# 2_matrix.net
KiCad netlist of a schematic drawn in Altium Designer
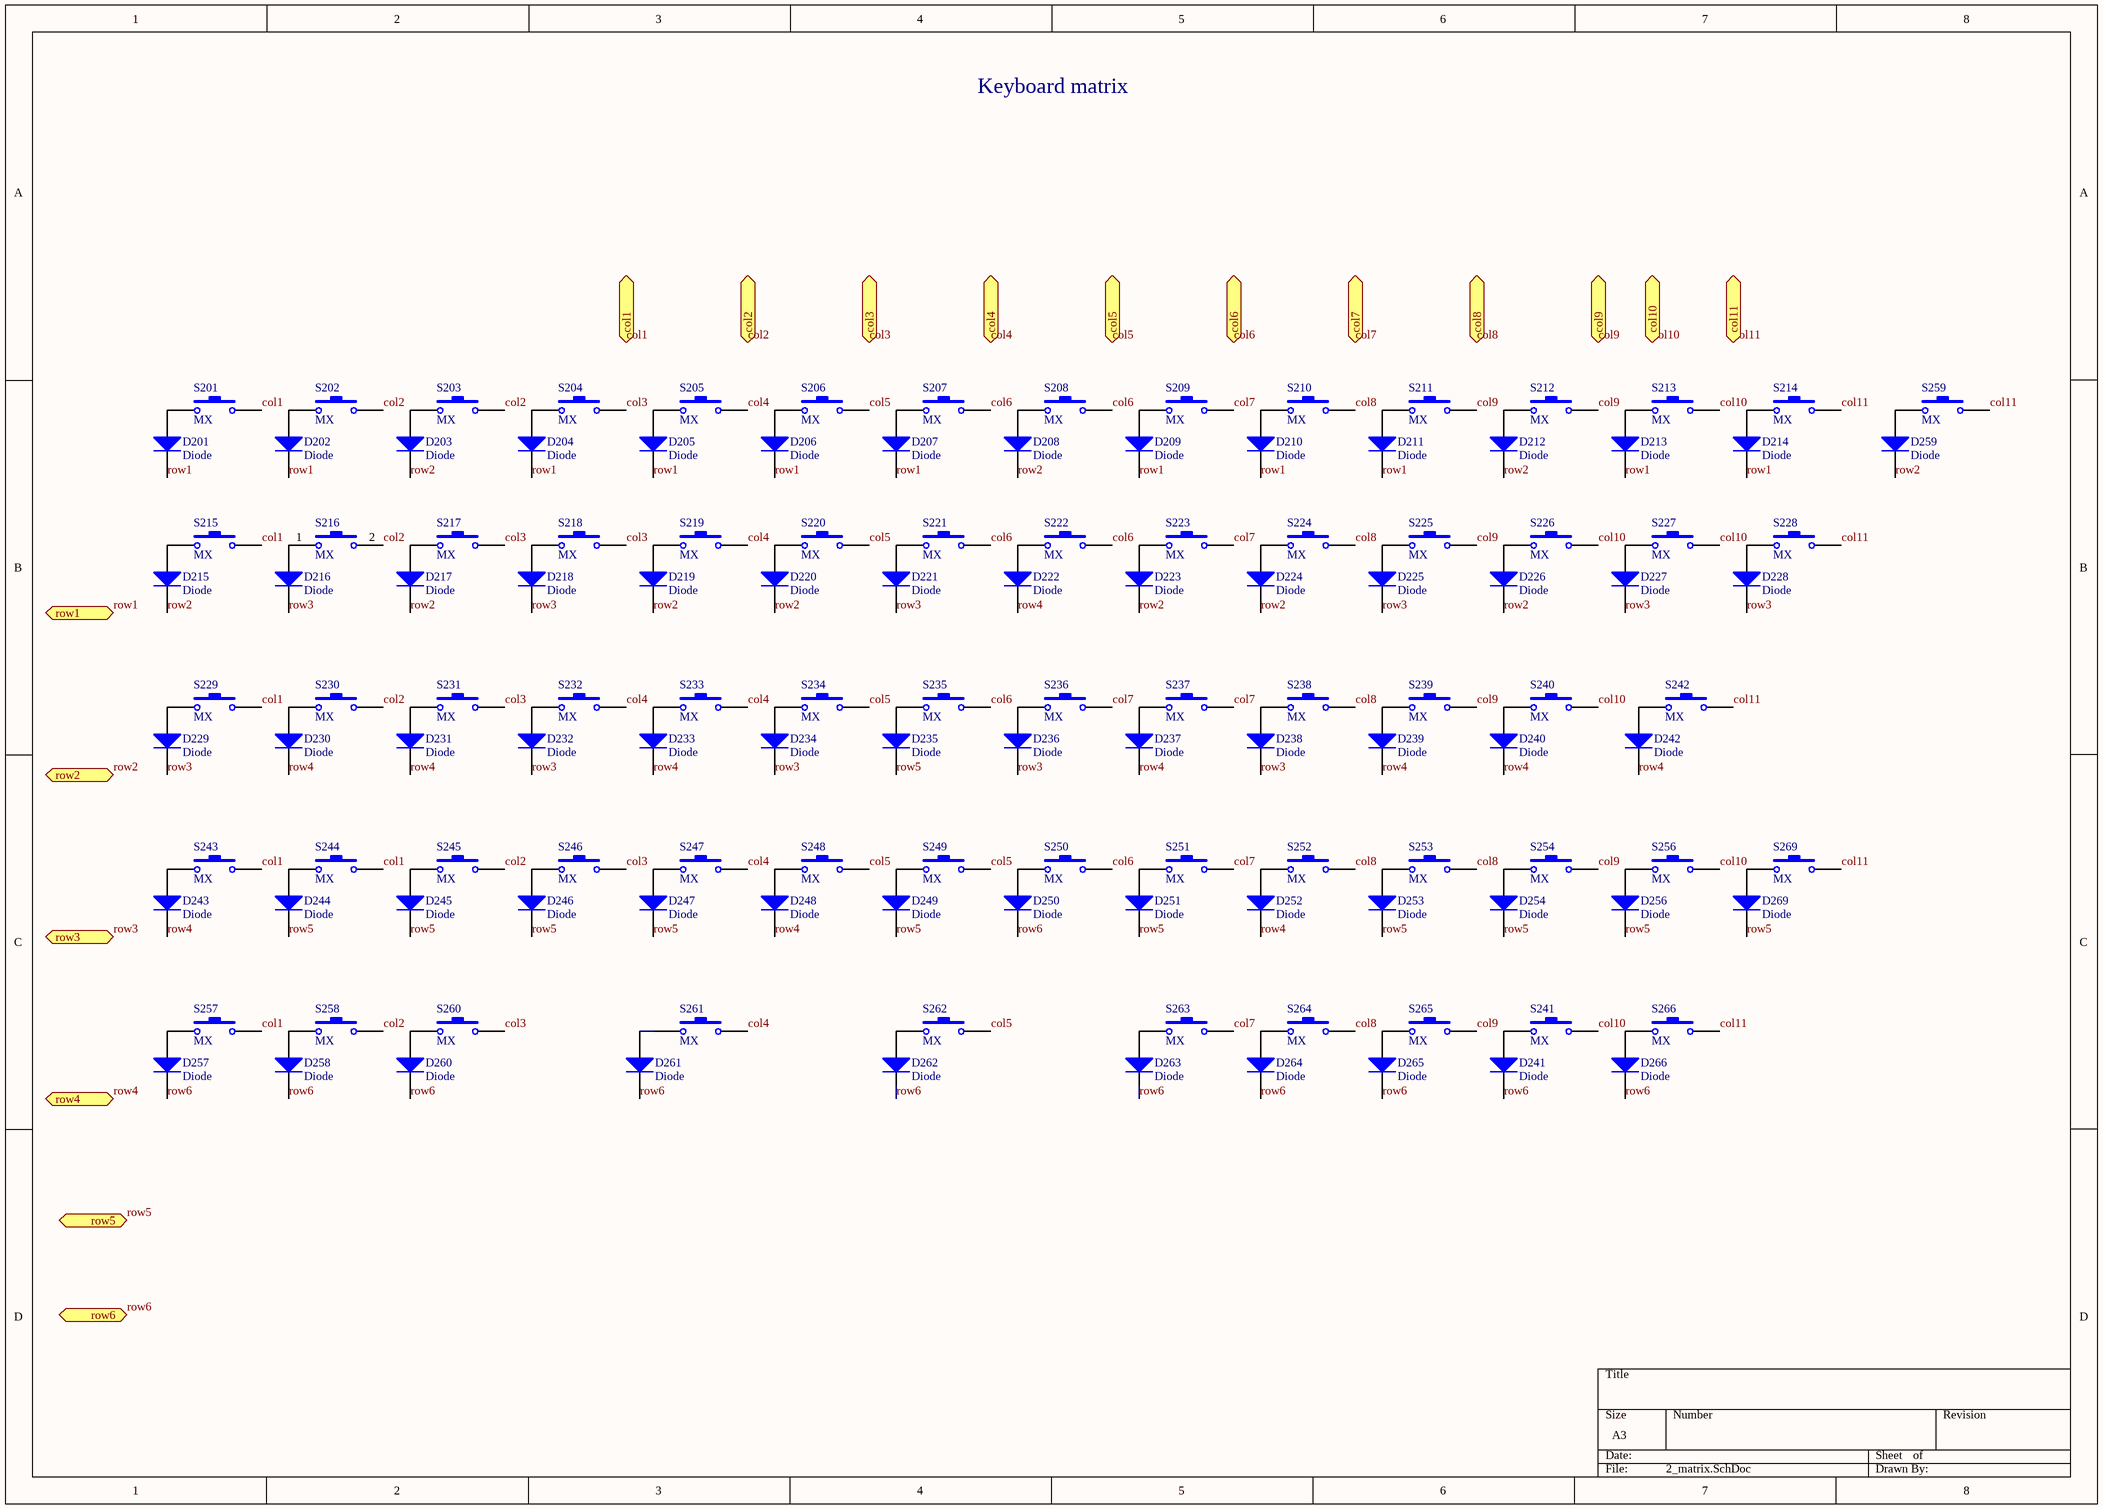
[diagram p0: 2_matrix.SchDoc]

(export (version "E")
  (design (tool "Eeschema 10.0.6"))
  (components
    (comp (ref "D201")
      (value "Diode")
      (footprint "D0603[1608]")
      (description "Default Diode")
      (fields (field (name "MFG") "Bourns Inc.") (field (name "MRF.PART") "CD4148WTP"))
      (libsource (lib "Miscellaneous Devices") (part "Diode"))
    )
    (comp (ref "D202")
      (value "Diode")
      (footprint "D0603[1608]")
      (description "Default Diode")
      (fields (field (name "MFG") "Bourns Inc.") (field (name "MRF.PART") "CD4148WTP"))
      (libsource (lib "Miscellaneous Devices") (part "Diode"))
    )
    (comp (ref "D203")
      (value "Diode")
      (footprint "D0603[1608]")
      (description "Default Diode")
      (fields (field (name "MFG") "Bourns Inc.") (field (name "MRF.PART") "CD4148WTP"))
      (libsource (lib "Miscellaneous Devices") (part "Diode"))
    )
    (comp (ref "D204")
      (value "Diode")
      (footprint "D0603[1608]")
      (description "Default Diode")
      (fields (field (name "MFG") "Bourns Inc.") (field (name "MRF.PART") "CD4148WTP"))
      (libsource (lib "Miscellaneous Devices") (part "Diode"))
    )
    (comp (ref "D205")
      (value "Diode")
      (footprint "D0603[1608]")
      (description "Default Diode")
      (fields (field (name "MFG") "Bourns Inc.") (field (name "MRF.PART") "CD4148WTP"))
      (libsource (lib "Miscellaneous Devices") (part "Diode"))
    )
    (comp (ref "D206")
      (value "Diode")
      (footprint "D0603[1608]")
      (description "Default Diode")
      (fields (field (name "MFG") "Bourns Inc.") (field (name "MRF.PART") "CD4148WTP"))
      (libsource (lib "Miscellaneous Devices") (part "Diode"))
    )
    (comp (ref "D207")
      (value "Diode")
      (footprint "D0603[1608]")
      (description "Default Diode")
      (fields (field (name "MFG") "Bourns Inc.") (field (name "MRF.PART") "CD4148WTP"))
      (libsource (lib "Miscellaneous Devices") (part "Diode"))
    )
    (comp (ref "D208")
      (value "Diode")
      (footprint "D0603[1608]")
      (description "Default Diode")
      (fields (field (name "MFG") "Bourns Inc.") (field (name "MRF.PART") "CD4148WTP"))
      (libsource (lib "Miscellaneous Devices") (part "Diode"))
    )
    (comp (ref "D209")
      (value "Diode")
      (footprint "D0603[1608]")
      (description "Default Diode")
      (fields (field (name "MFG") "Bourns Inc.") (field (name "MRF.PART") "CD4148WTP"))
      (libsource (lib "Miscellaneous Devices") (part "Diode"))
    )
    (comp (ref "D210")
      (value "Diode")
      (footprint "D0603[1608]")
      (description "Default Diode")
      (fields (field (name "MFG") "Bourns Inc.") (field (name "MRF.PART") "CD4148WTP"))
      (libsource (lib "Miscellaneous Devices") (part "Diode"))
    )
    (comp (ref "D211")
      (value "Diode")
      (footprint "D0603[1608]")
      (description "Default Diode")
      (fields (field (name "MFG") "Bourns Inc.") (field (name "MRF.PART") "CD4148WTP"))
      (libsource (lib "Miscellaneous Devices") (part "Diode"))
    )
    (comp (ref "D212")
      (value "Diode")
      (footprint "D0603[1608]")
      (description "Default Diode")
      (fields (field (name "MFG") "Bourns Inc.") (field (name "MRF.PART") "CD4148WTP"))
      (libsource (lib "Miscellaneous Devices") (part "Diode"))
    )
    (comp (ref "D213")
      (value "Diode")
      (footprint "D0603[1608]")
      (description "Default Diode")
      (fields (field (name "MFG") "Bourns Inc.") (field (name "MRF.PART") "CD4148WTP"))
      (libsource (lib "Miscellaneous Devices") (part "Diode"))
    )
    (comp (ref "D214")
      (value "Diode")
      (footprint "D0603[1608]")
      (description "Default Diode")
      (fields (field (name "MFG") "Bourns Inc.") (field (name "MRF.PART") "CD4148WTP"))
      (libsource (lib "Miscellaneous Devices") (part "Diode"))
    )
    (comp (ref "D215")
      (value "Diode")
      (footprint "D0603[1608]")
      (description "Default Diode")
      (fields (field (name "MFG") "Bourns Inc.") (field (name "MRF.PART") "CD4148WTP"))
      (libsource (lib "Miscellaneous Devices") (part "Diode"))
    )
    (comp (ref "D216")
      (value "Diode")
      (footprint "D0603[1608]")
      (description "Default Diode")
      (fields (field (name "MFG") "Bourns Inc.") (field (name "MRF.PART") "CD4148WTP"))
      (libsource (lib "Miscellaneous Devices") (part "Diode"))
    )
    (comp (ref "D217")
      (value "Diode")
      (footprint "D0603[1608]")
      (description "Default Diode")
      (fields (field (name "MFG") "Bourns Inc.") (field (name "MRF.PART") "CD4148WTP"))
      (libsource (lib "Miscellaneous Devices") (part "Diode"))
    )
    (comp (ref "D218")
      (value "Diode")
      (footprint "D0603[1608]")
      (description "Default Diode")
      (fields (field (name "MFG") "Bourns Inc.") (field (name "MRF.PART") "CD4148WTP"))
      (libsource (lib "Miscellaneous Devices") (part "Diode"))
    )
    (comp (ref "D219")
      (value "Diode")
      (footprint "D0603[1608]")
      (description "Default Diode")
      (fields (field (name "MFG") "Bourns Inc.") (field (name "MRF.PART") "CD4148WTP"))
      (libsource (lib "Miscellaneous Devices") (part "Diode"))
    )
    (comp (ref "D220")
      (value "Diode")
      (footprint "D0603[1608]")
      (description "Default Diode")
      (fields (field (name "MFG") "Bourns Inc.") (field (name "MRF.PART") "CD4148WTP"))
      (libsource (lib "Miscellaneous Devices") (part "Diode"))
    )
    (comp (ref "D221")
      (value "Diode")
      (footprint "D0603[1608]")
      (description "Default Diode")
      (fields (field (name "MFG") "Bourns Inc.") (field (name "MRF.PART") "CD4148WTP"))
      (libsource (lib "Miscellaneous Devices") (part "Diode"))
    )
    (comp (ref "D222")
      (value "Diode")
      (footprint "D0603[1608]")
      (description "Default Diode")
      (fields (field (name "MFG") "Bourns Inc.") (field (name "MRF.PART") "CD4148WTP"))
      (libsource (lib "Miscellaneous Devices") (part "Diode"))
    )
    (comp (ref "D223")
      (value "Diode")
      (footprint "D0603[1608]")
      (description "Default Diode")
      (fields (field (name "MFG") "Bourns Inc.") (field (name "MRF.PART") "CD4148WTP"))
      (libsource (lib "Miscellaneous Devices") (part "Diode"))
    )
    (comp (ref "D224")
      (value "Diode")
      (footprint "D0603[1608]")
      (description "Default Diode")
      (fields (field (name "MFG") "Bourns Inc.") (field (name "MRF.PART") "CD4148WTP"))
      (libsource (lib "Miscellaneous Devices") (part "Diode"))
    )
    (comp (ref "D225")
      (value "Diode")
      (footprint "D0603[1608]")
      (description "Default Diode")
      (fields (field (name "MFG") "Bourns Inc.") (field (name "MRF.PART") "CD4148WTP"))
      (libsource (lib "Miscellaneous Devices") (part "Diode"))
    )
    (comp (ref "D226")
      (value "Diode")
      (footprint "D0603[1608]")
      (description "Default Diode")
      (fields (field (name "MFG") "Bourns Inc.") (field (name "MRF.PART") "CD4148WTP"))
      (libsource (lib "Miscellaneous Devices") (part "Diode"))
    )
    (comp (ref "D227")
      (value "Diode")
      (footprint "D0603[1608]")
      (description "Default Diode")
      (fields (field (name "MFG") "Bourns Inc.") (field (name "MRF.PART") "CD4148WTP"))
      (libsource (lib "Miscellaneous Devices") (part "Diode"))
    )
    (comp (ref "D228")
      (value "Diode")
      (footprint "D0603[1608]")
      (description "Default Diode")
      (fields (field (name "MFG") "Bourns Inc.") (field (name "MRF.PART") "CD4148WTP"))
      (libsource (lib "Miscellaneous Devices") (part "Diode"))
    )
    (comp (ref "D229")
      (value "Diode")
      (footprint "D0603[1608]")
      (description "Default Diode")
      (fields (field (name "MFG") "Bourns Inc.") (field (name "MRF.PART") "CD4148WTP"))
      (libsource (lib "Miscellaneous Devices") (part "Diode"))
    )
    (comp (ref "D230")
      (value "Diode")
      (footprint "D0603[1608]")
      (description "Default Diode")
      (fields (field (name "MFG") "Bourns Inc.") (field (name "MRF.PART") "CD4148WTP"))
      (libsource (lib "Miscellaneous Devices") (part "Diode"))
    )
    (comp (ref "D231")
      (value "Diode")
      (footprint "D0603[1608]")
      (description "Default Diode")
      (fields (field (name "MFG") "Bourns Inc.") (field (name "MRF.PART") "CD4148WTP"))
      (libsource (lib "Miscellaneous Devices") (part "Diode"))
    )
    (comp (ref "D232")
      (value "Diode")
      (footprint "D0603[1608]")
      (description "Default Diode")
      (fields (field (name "MFG") "Bourns Inc.") (field (name "MRF.PART") "CD4148WTP"))
      (libsource (lib "Miscellaneous Devices") (part "Diode"))
    )
    (comp (ref "D233")
      (value "Diode")
      (footprint "D0603[1608]")
      (description "Default Diode")
      (fields (field (name "MFG") "Bourns Inc.") (field (name "MRF.PART") "CD4148WTP"))
      (libsource (lib "Miscellaneous Devices") (part "Diode"))
    )
    (comp (ref "D234")
      (value "Diode")
      (footprint "D0603[1608]")
      (description "Default Diode")
      (fields (field (name "MFG") "Bourns Inc.") (field (name "MRF.PART") "CD4148WTP"))
      (libsource (lib "Miscellaneous Devices") (part "Diode"))
    )
    (comp (ref "D235")
      (value "Diode")
      (footprint "D0603[1608]")
      (description "Default Diode")
      (fields (field (name "MFG") "Bourns Inc.") (field (name "MRF.PART") "CD4148WTP"))
      (libsource (lib "Miscellaneous Devices") (part "Diode"))
    )
    (comp (ref "D236")
      (value "Diode")
      (footprint "D0603[1608]")
      (description "Default Diode")
      (fields (field (name "MFG") "Bourns Inc.") (field (name "MRF.PART") "CD4148WTP"))
      (libsource (lib "Miscellaneous Devices") (part "Diode"))
    )
    (comp (ref "D237")
      (value "Diode")
      (footprint "D0603[1608]")
      (description "Default Diode")
      (fields (field (name "MFG") "Bourns Inc.") (field (name "MRF.PART") "CD4148WTP"))
      (libsource (lib "Miscellaneous Devices") (part "Diode"))
    )
    (comp (ref "D238")
      (value "Diode")
      (footprint "D0603[1608]")
      (description "Default Diode")
      (fields (field (name "MFG") "Bourns Inc.") (field (name "MRF.PART") "CD4148WTP"))
      (libsource (lib "Miscellaneous Devices") (part "Diode"))
    )
    (comp (ref "D239")
      (value "Diode")
      (footprint "D0603[1608]")
      (description "Default Diode")
      (fields (field (name "MFG") "Bourns Inc.") (field (name "MRF.PART") "CD4148WTP"))
      (libsource (lib "Miscellaneous Devices") (part "Diode"))
    )
    (comp (ref "D240")
      (value "Diode")
      (footprint "D0603[1608]")
      (description "Default Diode")
      (fields (field (name "MFG") "Bourns Inc.") (field (name "MRF.PART") "CD4148WTP"))
      (libsource (lib "Miscellaneous Devices") (part "Diode"))
    )
    (comp (ref "D241")
      (value "Diode")
      (footprint "D0603[1608]")
      (description "Default Diode")
      (fields (field (name "MFG") "Bourns Inc.") (field (name "MRF.PART") "CD4148WTP"))
      (libsource (lib "Miscellaneous Devices") (part "Diode"))
    )
    (comp (ref "D242")
      (value "Diode")
      (footprint "D0603[1608]")
      (description "Default Diode")
      (fields (field (name "MFG") "Bourns Inc.") (field (name "MRF.PART") "CD4148WTP"))
      (libsource (lib "Miscellaneous Devices") (part "Diode"))
    )
    (comp (ref "D243")
      (value "Diode")
      (footprint "D0603[1608]")
      (description "Default Diode")
      (fields (field (name "MFG") "Bourns Inc.") (field (name "MRF.PART") "CD4148WTP"))
      (libsource (lib "Miscellaneous Devices") (part "Diode"))
    )
    (comp (ref "D244")
      (value "Diode")
      (footprint "D0603[1608]")
      (description "Default Diode")
      (fields (field (name "MFG") "Bourns Inc.") (field (name "MRF.PART") "CD4148WTP"))
      (libsource (lib "Miscellaneous Devices") (part "Diode"))
    )
    (comp (ref "D245")
      (value "Diode")
      (footprint "D0603[1608]")
      (description "Default Diode")
      (fields (field (name "MFG") "Bourns Inc.") (field (name "MRF.PART") "CD4148WTP"))
      (libsource (lib "Miscellaneous Devices") (part "Diode"))
    )
    (comp (ref "D246")
      (value "Diode")
      (footprint "D0603[1608]")
      (description "Default Diode")
      (fields (field (name "MFG") "Bourns Inc.") (field (name "MRF.PART") "CD4148WTP"))
      (libsource (lib "Miscellaneous Devices") (part "Diode"))
    )
    (comp (ref "D247")
      (value "Diode")
      (footprint "D0603[1608]")
      (description "Default Diode")
      (fields (field (name "MFG") "Bourns Inc.") (field (name "MRF.PART") "CD4148WTP"))
      (libsource (lib "Miscellaneous Devices") (part "Diode"))
    )
    (comp (ref "D248")
      (value "Diode")
      (footprint "D0603[1608]")
      (description "Default Diode")
      (fields (field (name "MFG") "Bourns Inc.") (field (name "MRF.PART") "CD4148WTP"))
      (libsource (lib "Miscellaneous Devices") (part "Diode"))
    )
    (comp (ref "D249")
      (value "Diode")
      (footprint "D0603[1608]")
      (description "Default Diode")
      (fields (field (name "MFG") "Bourns Inc.") (field (name "MRF.PART") "CD4148WTP"))
      (libsource (lib "Miscellaneous Devices") (part "Diode"))
    )
    (comp (ref "D250")
      (value "Diode")
      (footprint "D0603[1608]")
      (description "Default Diode")
      (fields (field (name "MFG") "Bourns Inc.") (field (name "MRF.PART") "CD4148WTP"))
      (libsource (lib "Miscellaneous Devices") (part "Diode"))
    )
    (comp (ref "D251")
      (value "Diode")
      (footprint "D0603[1608]")
      (description "Default Diode")
      (fields (field (name "MFG") "Bourns Inc.") (field (name "MRF.PART") "CD4148WTP"))
      (libsource (lib "Miscellaneous Devices") (part "Diode"))
    )
    (comp (ref "D252")
      (value "Diode")
      (footprint "D0603[1608]")
      (description "Default Diode")
      (fields (field (name "MFG") "Bourns Inc.") (field (name "MRF.PART") "CD4148WTP"))
      (libsource (lib "Miscellaneous Devices") (part "Diode"))
    )
    (comp (ref "D253")
      (value "Diode")
      (footprint "D0603[1608]")
      (description "Default Diode")
      (fields (field (name "MFG") "Bourns Inc.") (field (name "MRF.PART") "CD4148WTP"))
      (libsource (lib "Miscellaneous Devices") (part "Diode"))
    )
    (comp (ref "D254")
      (value "Diode")
      (footprint "D0603[1608]")
      (description "Default Diode")
      (fields (field (name "MFG") "Bourns Inc.") (field (name "MRF.PART") "CD4148WTP"))
      (libsource (lib "Miscellaneous Devices") (part "Diode"))
    )
    (comp (ref "D256")
      (value "Diode")
      (footprint "D0603[1608]")
      (description "Default Diode")
      (fields (field (name "MFG") "Bourns Inc.") (field (name "MRF.PART") "CD4148WTP"))
      (libsource (lib "Miscellaneous Devices") (part "Diode"))
    )
    (comp (ref "D257")
      (value "Diode")
      (footprint "D0603[1608]")
      (description "Default Diode")
      (fields (field (name "MFG") "Bourns Inc.") (field (name "MRF.PART") "CD4148WTP"))
      (libsource (lib "Miscellaneous Devices") (part "Diode"))
    )
    (comp (ref "D258")
      (value "Diode")
      (footprint "D0603[1608]")
      (description "Default Diode")
      (fields (field (name "MFG") "Bourns Inc.") (field (name "MRF.PART") "CD4148WTP"))
      (libsource (lib "Miscellaneous Devices") (part "Diode"))
    )
    (comp (ref "D259")
      (value "Diode")
      (footprint "D0603[1608]")
      (description "Default Diode")
      (fields (field (name "MFG") "Bourns Inc.") (field (name "MRF.PART") "CD4148WTP"))
      (libsource (lib "Miscellaneous Devices") (part "Diode"))
    )
    (comp (ref "D260")
      (value "Diode")
      (footprint "D0603[1608]")
      (description "Default Diode")
      (fields (field (name "MFG") "Bourns Inc.") (field (name "MRF.PART") "CD4148WTP"))
      (libsource (lib "Miscellaneous Devices") (part "Diode"))
    )
    (comp (ref "D261")
      (value "Diode")
      (footprint "D0603[1608]")
      (description "Default Diode")
      (fields (field (name "MFG") "Bourns Inc.") (field (name "MRF.PART") "CD4148WTP"))
      (libsource (lib "Miscellaneous Devices") (part "Diode"))
    )
    (comp (ref "D262")
      (value "Diode")
      (footprint "D0603[1608]")
      (description "Default Diode")
      (fields (field (name "MFG") "Bourns Inc.") (field (name "MRF.PART") "CD4148WTP"))
      (libsource (lib "Miscellaneous Devices") (part "Diode"))
    )
    (comp (ref "D263")
      (value "Diode")
      (footprint "D0603[1608]")
      (description "Default Diode")
      (fields (field (name "MFG") "Bourns Inc.") (field (name "MRF.PART") "CD4148WTP"))
      (libsource (lib "Miscellaneous Devices") (part "Diode"))
    )
    (comp (ref "D264")
      (value "Diode")
      (footprint "D0603[1608]")
      (description "Default Diode")
      (fields (field (name "MFG") "Bourns Inc.") (field (name "MRF.PART") "CD4148WTP"))
      (libsource (lib "Miscellaneous Devices") (part "Diode"))
    )
    (comp (ref "D265")
      (value "Diode")
      (footprint "D0603[1608]")
      (description "Default Diode")
      (fields (field (name "MFG") "Bourns Inc.") (field (name "MRF.PART") "CD4148WTP"))
      (libsource (lib "Miscellaneous Devices") (part "Diode"))
    )
    (comp (ref "D266")
      (value "Diode")
      (footprint "D0603[1608]")
      (description "Default Diode")
      (fields (field (name "MFG") "Bourns Inc.") (field (name "MRF.PART") "CD4148WTP"))
      (libsource (lib "Miscellaneous Devices") (part "Diode"))
    )
    (comp (ref "D269")
      (value "Diode")
      (footprint "D0603[1608]")
      (description "Default Diode")
      (fields (field (name "MFG") "Bourns Inc.") (field (name "MRF.PART") "CD4148WTP"))
      (libsource (lib "Miscellaneous Devices") (part "Diode"))
    )
    (comp (ref "S201")
      (value "MX")
      (footprint "MXHS-switch")
      (description "Switch")
      (libsource (lib "Miscellaneous Devices") (part "SW-PB"))
    )
    (comp (ref "S202")
      (value "MX")
      (footprint "MXHS-switch")
      (description "Switch")
      (libsource (lib "Miscellaneous Devices") (part "SW-PB"))
    )
    (comp (ref "S203")
      (value "MX")
      (footprint "MXHS-switch")
      (description "Switch")
      (libsource (lib "Miscellaneous Devices") (part "SW-PB"))
    )
    (comp (ref "S204")
      (value "MX")
      (footprint "MXHS-switch")
      (description "Switch")
      (libsource (lib "Miscellaneous Devices") (part "SW-PB"))
    )
    (comp (ref "S205")
      (value "MX")
      (footprint "MXHS-switch")
      (description "Switch")
      (libsource (lib "Miscellaneous Devices") (part "SW-PB"))
    )
    (comp (ref "S206")
      (value "MX")
      (footprint "MXHS-switch")
      (description "Switch")
      (libsource (lib "Miscellaneous Devices") (part "SW-PB"))
    )
    (comp (ref "S207")
      (value "MX")
      (footprint "MXHS-switch_Switched_Pol")
      (description "Switch")
      (libsource (lib "Miscellaneous Devices") (part "SW-PB"))
    )
    (comp (ref "S208")
      (value "MX")
      (footprint "MXHS-switch")
      (description "Switch")
      (libsource (lib "Miscellaneous Devices") (part "SW-PB"))
    )
    (comp (ref "S209")
      (value "MX")
      (footprint "MXHS-switch")
      (description "Switch")
      (libsource (lib "Miscellaneous Devices") (part "SW-PB"))
    )
    (comp (ref "S210")
      (value "MX")
      (footprint "MXHS-switch")
      (description "Switch")
      (libsource (lib "Miscellaneous Devices") (part "SW-PB"))
    )
    (comp (ref "S211")
      (value "MX")
      (footprint "MXHS-switch_Switched_Pol")
      (description "Switch")
      (libsource (lib "Miscellaneous Devices") (part "SW-PB"))
    )
    (comp (ref "S212")
      (value "MX")
      (footprint "MXHS-switch")
      (description "Switch")
      (libsource (lib "Miscellaneous Devices") (part "SW-PB"))
    )
    (comp (ref "S213")
      (value "MX")
      (footprint "MXHS-switch")
      (description "Switch")
      (libsource (lib "Miscellaneous Devices") (part "SW-PB"))
    )
    (comp (ref "S214")
      (value "MX")
      (footprint "MXHS-switch")
      (description "Switch")
      (libsource (lib "Miscellaneous Devices") (part "SW-PB"))
    )
    (comp (ref "S215")
      (value "MX")
      (footprint "MXHS-SWITCH - 1.5U")
      (description "TAB")
      (libsource (lib "Miscellaneous Devices") (part "SW-PB"))
    )
    (comp (ref "S216")
      (value "MX")
      (footprint "MXHS-switch")
      (description "Switch")
      (libsource (lib "") (part "SW-PB_1"))
    )
    (comp (ref "S217")
      (value "MX")
      (footprint "MXHS-switch")
      (description "Switch")
      (libsource (lib "Miscellaneous Devices") (part "SW-PB"))
    )
    (comp (ref "S218")
      (value "MX")
      (footprint "MXHS-switch")
      (description "Switch")
      (libsource (lib "Miscellaneous Devices") (part "SW-PB"))
    )
    (comp (ref "S219")
      (value "MX")
      (footprint "MXHS-switch")
      (description "Switch")
      (libsource (lib "Miscellaneous Devices") (part "SW-PB"))
    )
    (comp (ref "S220")
      (value "MX")
      (footprint "MXHS-switch")
      (description "Switch")
      (libsource (lib "Miscellaneous Devices") (part "SW-PB"))
    )
    (comp (ref "S221")
      (value "MX")
      (footprint "MXHS-switch")
      (description "Switch")
      (libsource (lib "Miscellaneous Devices") (part "SW-PB"))
    )
    (comp (ref "S222")
      (value "MX")
      (footprint "MXHS-switch")
      (description "Switch")
      (libsource (lib "Miscellaneous Devices") (part "SW-PB"))
    )
    (comp (ref "S223")
      (value "MX")
      (footprint "MXHS-switch")
      (description "Switch")
      (libsource (lib "Miscellaneous Devices") (part "SW-PB"))
    )
    (comp (ref "S224")
      (value "MX")
      (footprint "MXHS-switch")
      (description "Switch")
      (libsource (lib "Miscellaneous Devices") (part "SW-PB"))
    )
    (comp (ref "S225")
      (value "MX")
      (footprint "MXHS-switch")
      (description "Switch")
      (libsource (lib "Miscellaneous Devices") (part "SW-PB"))
    )
    (comp (ref "S226")
      (value "MX")
      (footprint "MXHS-switch_Switched_Pol")
      (description "Switch")
      (libsource (lib "Miscellaneous Devices") (part "SW-PB"))
    )
    (comp (ref "S227")
      (value "MX")
      (footprint "MXHS-switch")
      (description "Switch")
      (libsource (lib "Miscellaneous Devices") (part "SW-PB"))
    )
    (comp (ref "S228")
      (value "MX")
      (footprint "MXHS-SWITCH - PIPE_ISO_ENTER_V2")
      (description "Switch")
      (libsource (lib "Miscellaneous Devices") (part "SW-PB"))
    )
    (comp (ref "S229")
      (value "MX")
      (footprint "MXHS-SWITCH - CAPS_STEPPED_DUAL")
      (description "Switch")
      (libsource (lib "Miscellaneous Devices") (part "SW-PB"))
    )
    (comp (ref "S230")
      (value "MX")
      (footprint "MXHS-switch")
      (description "Switch")
      (libsource (lib "Miscellaneous Devices") (part "SW-PB"))
    )
    (comp (ref "S231")
      (value "MX")
      (footprint "MXHS-switch")
      (description "Switch")
      (libsource (lib "Miscellaneous Devices") (part "SW-PB"))
    )
    (comp (ref "S232")
      (value "MX")
      (footprint "MXHS-switch_Switched_Pol")
      (description "Switch")
      (libsource (lib "Miscellaneous Devices") (part "SW-PB"))
    )
    (comp (ref "S233")
      (value "MX")
      (footprint "MXHS-switch")
      (description "Switch")
      (libsource (lib "Miscellaneous Devices") (part "SW-PB"))
    )
    (comp (ref "S234")
      (value "MX")
      (footprint "MXHS-switch")
      (description "Switch")
      (libsource (lib "Miscellaneous Devices") (part "SW-PB"))
    )
    (comp (ref "S235")
      (value "MX")
      (footprint "MXHS-switch")
      (description "Switch")
      (libsource (lib "Miscellaneous Devices") (part "SW-PB"))
    )
    (comp (ref "S236")
      (value "MX")
      (footprint "MXHS-switch_Switched_Pol")
      (description "Switch")
      (libsource (lib "Miscellaneous Devices") (part "SW-PB"))
    )
    (comp (ref "S237")
      (value "MX")
      (footprint "MXHS-switch")
      (description "Switch")
      (libsource (lib "Miscellaneous Devices") (part "SW-PB"))
    )
    (comp (ref "S238")
      (value "MX")
      (footprint "MXHS-switch")
      (description "Switch")
      (libsource (lib "Miscellaneous Devices") (part "SW-PB"))
    )
    (comp (ref "S239")
      (value "MX")
      (footprint "MXHS-switch")
      (description "Switch")
      (libsource (lib "Miscellaneous Devices") (part "SW-PB"))
    )
    (comp (ref "S240")
      (value "MX")
      (footprint "MXHS-switch")
      (description "Switch")
      (libsource (lib "Miscellaneous Devices") (part "SW-PB"))
    )
    (comp (ref "S241")
      (value "MX")
      (footprint "MXHS-SWITCH - R_WIN")
      (description "Switch")
      (libsource (lib "Miscellaneous Devices") (part "SW-PB"))
    )
    (comp (ref "S242")
      (value "MX")
      (footprint "MXHS-SWITCH - ENTER_ANSI_ISO_KEY")
      (description "Switch")
      (libsource (lib "Miscellaneous Devices") (part "SW-PB"))
    )
    (comp (ref "S243")
      (value "MX")
      (footprint "MXHS-switch - Left shift")
      (description "Switch")
      (libsource (lib "Miscellaneous Devices") (part "SW-PB"))
    )
    (comp (ref "S244")
      (value "MX")
      (footprint "MXHS-switch")
      (description "Switch")
      (libsource (lib "Miscellaneous Devices") (part "SW-PB"))
    )
    (comp (ref "S245")
      (value "MX")
      (footprint "MXHS-switch")
      (description "Switch")
      (libsource (lib "Miscellaneous Devices") (part "SW-PB"))
    )
    (comp (ref "S246")
      (value "MX")
      (footprint "MXHS-switch")
      (description "Switch")
      (libsource (lib "Miscellaneous Devices") (part "SW-PB"))
    )
    (comp (ref "S247")
      (value "MX")
      (footprint "MXHS-switch_Switched_Pol")
      (description "Switch")
      (libsource (lib "Miscellaneous Devices") (part "SW-PB"))
    )
    (comp (ref "S248")
      (value "MX")
      (footprint "MXHS-switch_Switched_Pol")
      (description "Switch")
      (libsource (lib "Miscellaneous Devices") (part "SW-PB"))
    )
    (comp (ref "S249")
      (value "MX")
      (footprint "MXHS-switch")
      (description "Switch")
      (libsource (lib "Miscellaneous Devices") (part "SW-PB"))
    )
    (comp (ref "S250")
      (value "MX")
      (footprint "MXHS-switch")
      (description "Switch")
      (libsource (lib "Miscellaneous Devices") (part "SW-PB"))
    )
    (comp (ref "S251")
      (value "MX")
      (footprint "MXHS-switch_Switched_Pol")
      (description "Switch")
      (libsource (lib "Miscellaneous Devices") (part "SW-PB"))
    )
    (comp (ref "S252")
      (value "MX")
      (footprint "MXHS-switch_Switched_Pol")
      (description "Switch")
      (libsource (lib "Miscellaneous Devices") (part "SW-PB"))
    )
    (comp (ref "S253")
      (value "MX")
      (footprint "MXHS-switch")
      (description "Switch")
      (libsource (lib "Miscellaneous Devices") (part "SW-PB"))
    )
    (comp (ref "S254")
      (value "MX")
      (footprint "MXHS-switch")
      (description "Switch")
      (libsource (lib "Miscellaneous Devices") (part "SW-PB"))
    )
    (comp (ref "S256")
      (value "MX")
      (footprint "MXHS-switch - right shift")
      (description "Switch")
      (libsource (lib "Miscellaneous Devices") (part "SW-PB"))
    )
    (comp (ref "S257")
      (value "MX")
      (footprint "MXHS-switch - L_CTRL")
      (description "Switch")
      (libsource (lib "Miscellaneous Devices") (part "SW-PB"))
    )
    (comp (ref "S258")
      (value "MX")
      (footprint "MXHS-switch - L_WIN")
      (description "Switch")
      (libsource (lib "Miscellaneous Devices") (part "SW-PB"))
    )
    (comp (ref "S259")
      (value "MX")
      (footprint "MXHS-switch - backspace")
      (description "Switch")
      (libsource (lib "Miscellaneous Devices") (part "SW-PB"))
    )
    (comp (ref "S260")
      (value "MX")
      (footprint "MXHS-switch - L_alt")
      (description "Switch")
      (libsource (lib "Miscellaneous Devices") (part "SW-PB"))
    )
    (comp (ref "S261")
      (value "MX")
      (footprint "MXHS-SWITCH - L SPLIT SPACE")
      (description "Switch")
      (libsource (lib "Miscellaneous Devices") (part "SW-PB"))
    )
    (comp (ref "S262")
      (value "MX")
      (footprint "MXHS-switch - Space_V2")
      (description "Switch")
      (libsource (lib "Miscellaneous Devices") (part "SW-PB"))
    )
    (comp (ref "S263")
      (value "MX")
      (footprint "MXHS-SWITCH - R SPLIT SPACE")
      (description "Switch")
      (libsource (lib "Miscellaneous Devices") (part "SW-PB"))
    )
    (comp (ref "S264")
      (value "MX")
      (footprint "MXHS-switch")
      (description "Switch")
      (libsource (lib "Miscellaneous Devices") (part "SW-PB"))
    )
    (comp (ref "S265")
      (value "MX")
      (footprint "MXHS-SWITCH - R_ALT_V2")
      (description "Switch")
      (libsource (lib "Miscellaneous Devices") (part "SW-PB"))
    )
    (comp (ref "S266")
      (value "MX")
      (footprint "MXHS-SWITCH - R_CTRL")
      (description "Switch")
      (libsource (lib "Miscellaneous Devices") (part "SW-PB"))
    )
    (comp (ref "S269")
      (value "MX")
      (footprint "MXHS-switch")
      (description "Switch")
      (libsource (lib "Miscellaneous Devices") (part "SW-PB"))
    )
  )
  (nets
    (net (code "1") (name "/col1") (class "Default")
      (node (ref "S201") (pin "2") (pinfunction "2_2") (pintype "passive"))
      (node (ref "S215") (pin "2") (pinfunction "2_2") (pintype "passive"))
      (node (ref "S229") (pin "2") (pinfunction "2_2") (pintype "passive"))
      (node (ref "S243") (pin "2") (pinfunction "2_2") (pintype "passive"))
      (node (ref "S244") (pin "2") (pinfunction "2_2") (pintype "passive"))
      (node (ref "S257") (pin "2") (pinfunction "2_2") (pintype "passive"))
    )
    (net (code "2") (name "/col2") (class "Default")
      (node (ref "S202") (pin "2") (pinfunction "2_2") (pintype "passive"))
      (node (ref "S203") (pin "2") (pinfunction "2_2") (pintype "passive"))
      (node (ref "S216") (pin "2") (pinfunction "2_2") (pintype "passive"))
      (node (ref "S230") (pin "2") (pinfunction "2_2") (pintype "passive"))
      (node (ref "S245") (pin "2") (pinfunction "2_2") (pintype "passive"))
      (node (ref "S258") (pin "2") (pinfunction "2_2") (pintype "passive"))
    )
    (net (code "3") (name "/col3") (class "Default")
      (node (ref "S204") (pin "2") (pinfunction "2_2") (pintype "passive"))
      (node (ref "S217") (pin "2") (pinfunction "2_2") (pintype "passive"))
      (node (ref "S218") (pin "2") (pinfunction "2_2") (pintype "passive"))
      (node (ref "S231") (pin "2") (pinfunction "2_2") (pintype "passive"))
      (node (ref "S246") (pin "2") (pinfunction "2_2") (pintype "passive"))
      (node (ref "S260") (pin "2") (pinfunction "2_2") (pintype "passive"))
    )
    (net (code "4") (name "/col4") (class "Default")
      (node (ref "S205") (pin "2") (pinfunction "2_2") (pintype "passive"))
      (node (ref "S219") (pin "2") (pinfunction "2_2") (pintype "passive"))
      (node (ref "S232") (pin "2") (pinfunction "2_2") (pintype "passive"))
      (node (ref "S233") (pin "2") (pinfunction "2_2") (pintype "passive"))
      (node (ref "S247") (pin "2") (pinfunction "2_2") (pintype "passive"))
      (node (ref "S261") (pin "2") (pinfunction "2_2") (pintype "passive"))
    )
    (net (code "5") (name "/col5") (class "Default")
      (node (ref "S206") (pin "2") (pinfunction "2_2") (pintype "passive"))
      (node (ref "S220") (pin "2") (pinfunction "2_2") (pintype "passive"))
      (node (ref "S234") (pin "2") (pinfunction "2_2") (pintype "passive"))
      (node (ref "S248") (pin "2") (pinfunction "2_2") (pintype "passive"))
      (node (ref "S249") (pin "2") (pinfunction "2_2") (pintype "passive"))
      (node (ref "S262") (pin "2") (pinfunction "2_2") (pintype "passive"))
    )
    (net (code "6") (name "/col6") (class "Default")
      (node (ref "S207") (pin "2") (pinfunction "2_2") (pintype "passive"))
      (node (ref "S208") (pin "2") (pinfunction "2_2") (pintype "passive"))
      (node (ref "S221") (pin "2") (pinfunction "2_2") (pintype "passive"))
      (node (ref "S222") (pin "2") (pinfunction "2_2") (pintype "passive"))
      (node (ref "S235") (pin "2") (pinfunction "2_2") (pintype "passive"))
      (node (ref "S250") (pin "2") (pinfunction "2_2") (pintype "passive"))
    )
    (net (code "7") (name "/col7") (class "Default")
      (node (ref "S209") (pin "2") (pinfunction "2_2") (pintype "passive"))
      (node (ref "S223") (pin "2") (pinfunction "2_2") (pintype "passive"))
      (node (ref "S236") (pin "2") (pinfunction "2_2") (pintype "passive"))
      (node (ref "S237") (pin "2") (pinfunction "2_2") (pintype "passive"))
      (node (ref "S251") (pin "2") (pinfunction "2_2") (pintype "passive"))
      (node (ref "S263") (pin "2") (pinfunction "2_2") (pintype "passive"))
    )
    (net (code "8") (name "/col8") (class "Default")
      (node (ref "S210") (pin "2") (pinfunction "2_2") (pintype "passive"))
      (node (ref "S224") (pin "2") (pinfunction "2_2") (pintype "passive"))
      (node (ref "S238") (pin "2") (pinfunction "2_2") (pintype "passive"))
      (node (ref "S252") (pin "2") (pinfunction "2_2") (pintype "passive"))
      (node (ref "S253") (pin "2") (pinfunction "2_2") (pintype "passive"))
      (node (ref "S264") (pin "2") (pinfunction "2_2") (pintype "passive"))
    )
    (net (code "9") (name "/col9") (class "Default")
      (node (ref "S211") (pin "2") (pinfunction "2_2") (pintype "passive"))
      (node (ref "S212") (pin "2") (pinfunction "2_2") (pintype "passive"))
      (node (ref "S225") (pin "2") (pinfunction "2_2") (pintype "passive"))
      (node (ref "S239") (pin "2") (pinfunction "2_2") (pintype "passive"))
      (node (ref "S254") (pin "2") (pinfunction "2_2") (pintype "passive"))
      (node (ref "S265") (pin "2") (pinfunction "2_2") (pintype "passive"))
    )
    (net (code "10") (name "/col10") (class "Default")
      (node (ref "S213") (pin "2") (pinfunction "2_2") (pintype "passive"))
      (node (ref "S226") (pin "2") (pinfunction "2_2") (pintype "passive"))
      (node (ref "S227") (pin "2") (pinfunction "2_2") (pintype "passive"))
      (node (ref "S240") (pin "2") (pinfunction "2_2") (pintype "passive"))
      (node (ref "S241") (pin "2") (pinfunction "2_2") (pintype "passive"))
      (node (ref "S256") (pin "2") (pinfunction "2_2") (pintype "passive"))
    )
    (net (code "11") (name "/col11") (class "Default")
      (node (ref "S214") (pin "2") (pinfunction "2_2") (pintype "passive"))
      (node (ref "S228") (pin "2") (pinfunction "2_2") (pintype "passive"))
      (node (ref "S242") (pin "2") (pinfunction "2_2") (pintype "passive"))
      (node (ref "S259") (pin "2") (pinfunction "2_2") (pintype "passive"))
      (node (ref "S266") (pin "2") (pinfunction "2_2") (pintype "passive"))
      (node (ref "S269") (pin "2") (pinfunction "2_2") (pintype "passive"))
    )
    (net (code "12") (name "/row1") (class "Default")
      (node (ref "D201") (pin "2") (pinfunction "K_2") (pintype "passive"))
      (node (ref "D202") (pin "2") (pinfunction "K_2") (pintype "passive"))
      (node (ref "D204") (pin "2") (pinfunction "K_2") (pintype "passive"))
      (node (ref "D205") (pin "2") (pinfunction "K_2") (pintype "passive"))
      (node (ref "D206") (pin "2") (pinfunction "K_2") (pintype "passive"))
      (node (ref "D207") (pin "2") (pinfunction "K_2") (pintype "passive"))
      (node (ref "D209") (pin "2") (pinfunction "K_2") (pintype "passive"))
      (node (ref "D210") (pin "2") (pinfunction "K_2") (pintype "passive"))
      (node (ref "D211") (pin "2") (pinfunction "K_2") (pintype "passive"))
      (node (ref "D213") (pin "2") (pinfunction "K_2") (pintype "passive"))
      (node (ref "D214") (pin "2") (pinfunction "K_2") (pintype "passive"))
    )
    (net (code "13") (name "/row2") (class "Default")
      (node (ref "D203") (pin "2") (pinfunction "K_2") (pintype "passive"))
      (node (ref "D208") (pin "2") (pinfunction "K_2") (pintype "passive"))
      (node (ref "D212") (pin "2") (pinfunction "K_2") (pintype "passive"))
      (node (ref "D215") (pin "2") (pinfunction "K_2") (pintype "passive"))
      (node (ref "D217") (pin "2") (pinfunction "K_2") (pintype "passive"))
      (node (ref "D219") (pin "2") (pinfunction "K_2") (pintype "passive"))
      (node (ref "D220") (pin "2") (pinfunction "K_2") (pintype "passive"))
      (node (ref "D223") (pin "2") (pinfunction "K_2") (pintype "passive"))
      (node (ref "D224") (pin "2") (pinfunction "K_2") (pintype "passive"))
      (node (ref "D226") (pin "2") (pinfunction "K_2") (pintype "passive"))
      (node (ref "D259") (pin "2") (pinfunction "K_2") (pintype "passive"))
    )
    (net (code "14") (name "/row3") (class "Default")
      (node (ref "D216") (pin "2") (pinfunction "K_2") (pintype "passive"))
      (node (ref "D218") (pin "2") (pinfunction "K_2") (pintype "passive"))
      (node (ref "D221") (pin "2") (pinfunction "K_2") (pintype "passive"))
      (node (ref "D225") (pin "2") (pinfunction "K_2") (pintype "passive"))
      (node (ref "D227") (pin "2") (pinfunction "K_2") (pintype "passive"))
      (node (ref "D228") (pin "2") (pinfunction "K_2") (pintype "passive"))
      (node (ref "D229") (pin "2") (pinfunction "K_2") (pintype "passive"))
      (node (ref "D232") (pin "2") (pinfunction "K_2") (pintype "passive"))
      (node (ref "D234") (pin "2") (pinfunction "K_2") (pintype "passive"))
      (node (ref "D236") (pin "2") (pinfunction "K_2") (pintype "passive"))
      (node (ref "D238") (pin "2") (pinfunction "K_2") (pintype "passive"))
    )
    (net (code "15") (name "/row4") (class "Default")
      (node (ref "D222") (pin "2") (pinfunction "K_2") (pintype "passive"))
      (node (ref "D230") (pin "2") (pinfunction "K_2") (pintype "passive"))
      (node (ref "D231") (pin "2") (pinfunction "K_2") (pintype "passive"))
      (node (ref "D233") (pin "2") (pinfunction "K_2") (pintype "passive"))
      (node (ref "D237") (pin "2") (pinfunction "K_2") (pintype "passive"))
      (node (ref "D239") (pin "2") (pinfunction "K_2") (pintype "passive"))
      (node (ref "D240") (pin "2") (pinfunction "K_2") (pintype "passive"))
      (node (ref "D242") (pin "2") (pinfunction "K_2") (pintype "passive"))
      (node (ref "D243") (pin "2") (pinfunction "K_2") (pintype "passive"))
      (node (ref "D248") (pin "2") (pinfunction "K_2") (pintype "passive"))
      (node (ref "D252") (pin "2") (pinfunction "K_2") (pintype "passive"))
    )
    (net (code "16") (name "/row5") (class "Default")
      (node (ref "D235") (pin "2") (pinfunction "K_2") (pintype "passive"))
      (node (ref "D244") (pin "2") (pinfunction "K_2") (pintype "passive"))
      (node (ref "D245") (pin "2") (pinfunction "K_2") (pintype "passive"))
      (node (ref "D246") (pin "2") (pinfunction "K_2") (pintype "passive"))
      (node (ref "D247") (pin "2") (pinfunction "K_2") (pintype "passive"))
      (node (ref "D249") (pin "2") (pinfunction "K_2") (pintype "passive"))
      (node (ref "D251") (pin "2") (pinfunction "K_2") (pintype "passive"))
      (node (ref "D253") (pin "2") (pinfunction "K_2") (pintype "passive"))
      (node (ref "D254") (pin "2") (pinfunction "K_2") (pintype "passive"))
      (node (ref "D256") (pin "2") (pinfunction "K_2") (pintype "passive"))
      (node (ref "D269") (pin "2") (pinfunction "K_2") (pintype "passive"))
    )
    (net (code "17") (name "/row6") (class "Default")
      (node (ref "D241") (pin "2") (pinfunction "K_2") (pintype "passive"))
      (node (ref "D250") (pin "2") (pinfunction "K_2") (pintype "passive"))
      (node (ref "D257") (pin "2") (pinfunction "K_2") (pintype "passive"))
      (node (ref "D258") (pin "2") (pinfunction "K_2") (pintype "passive"))
      (node (ref "D260") (pin "2") (pinfunction "K_2") (pintype "passive"))
      (node (ref "D261") (pin "2") (pinfunction "K_2") (pintype "passive"))
      (node (ref "D262") (pin "2") (pinfunction "K_2") (pintype "passive"))
      (node (ref "D263") (pin "2") (pinfunction "K_2") (pintype "passive"))
      (node (ref "D264") (pin "2") (pinfunction "K_2") (pintype "passive"))
      (node (ref "D265") (pin "2") (pinfunction "K_2") (pintype "passive"))
      (node (ref "D266") (pin "2") (pinfunction "K_2") (pintype "passive"))
    )
    (net (code "18") (name "Net-(D201-A)") (class "Default")
      (node (ref "D201") (pin "1") (pinfunction "A_1") (pintype "passive"))
      (node (ref "S201") (pin "1") (pinfunction "1_1") (pintype "passive"))
    )
    (net (code "19") (name "Net-(D202-A)") (class "Default")
      (node (ref "D202") (pin "1") (pinfunction "A_1") (pintype "passive"))
      (node (ref "S202") (pin "1") (pinfunction "1_1") (pintype "passive"))
    )
    (net (code "20") (name "Net-(D203-A)") (class "Default")
      (node (ref "D203") (pin "1") (pinfunction "A_1") (pintype "passive"))
      (node (ref "S203") (pin "1") (pinfunction "1_1") (pintype "passive"))
    )
    (net (code "21") (name "Net-(D204-A)") (class "Default")
      (node (ref "D204") (pin "1") (pinfunction "A_1") (pintype "passive"))
      (node (ref "S204") (pin "1") (pinfunction "1_1") (pintype "passive"))
    )
    (net (code "22") (name "Net-(D205-A)") (class "Default")
      (node (ref "D205") (pin "1") (pinfunction "A_1") (pintype "passive"))
      (node (ref "S205") (pin "1") (pinfunction "1_1") (pintype "passive"))
    )
    (net (code "23") (name "Net-(D206-A)") (class "Default")
      (node (ref "D206") (pin "1") (pinfunction "A_1") (pintype "passive"))
      (node (ref "S206") (pin "1") (pinfunction "1_1") (pintype "passive"))
    )
    (net (code "24") (name "Net-(D207-A)") (class "Default")
      (node (ref "D207") (pin "1") (pinfunction "A_1") (pintype "passive"))
      (node (ref "S207") (pin "1") (pinfunction "1_1") (pintype "passive"))
    )
    (net (code "25") (name "Net-(D208-A)") (class "Default")
      (node (ref "D208") (pin "1") (pinfunction "A_1") (pintype "passive"))
      (node (ref "S208") (pin "1") (pinfunction "1_1") (pintype "passive"))
    )
    (net (code "26") (name "Net-(D209-A)") (class "Default")
      (node (ref "D209") (pin "1") (pinfunction "A_1") (pintype "passive"))
      (node (ref "S209") (pin "1") (pinfunction "1_1") (pintype "passive"))
    )
    (net (code "27") (name "Net-(D210-A)") (class "Default")
      (node (ref "D210") (pin "1") (pinfunction "A_1") (pintype "passive"))
      (node (ref "S210") (pin "1") (pinfunction "1_1") (pintype "passive"))
    )
    (net (code "28") (name "Net-(D211-A)") (class "Default")
      (node (ref "D211") (pin "1") (pinfunction "A_1") (pintype "passive"))
      (node (ref "S211") (pin "1") (pinfunction "1_1") (pintype "passive"))
    )
    (net (code "29") (name "Net-(D212-A)") (class "Default")
      (node (ref "D212") (pin "1") (pinfunction "A_1") (pintype "passive"))
      (node (ref "S212") (pin "1") (pinfunction "1_1") (pintype "passive"))
    )
    (net (code "30") (name "Net-(D213-A)") (class "Default")
      (node (ref "D213") (pin "1") (pinfunction "A_1") (pintype "passive"))
      (node (ref "S213") (pin "1") (pinfunction "1_1") (pintype "passive"))
    )
    (net (code "31") (name "Net-(D214-A)") (class "Default")
      (node (ref "D214") (pin "1") (pinfunction "A_1") (pintype "passive"))
      (node (ref "S214") (pin "1") (pinfunction "1_1") (pintype "passive"))
    )
    (net (code "32") (name "Net-(D215-A)") (class "Default")
      (node (ref "D215") (pin "1") (pinfunction "A_1") (pintype "passive"))
      (node (ref "S215") (pin "1") (pinfunction "1_1") (pintype "passive"))
    )
    (net (code "33") (name "Net-(D216-A)") (class "Default")
      (node (ref "D216") (pin "1") (pinfunction "A_1") (pintype "passive"))
      (node (ref "S216") (pin "1") (pinfunction "1_1") (pintype "passive"))
    )
    (net (code "34") (name "Net-(D217-A)") (class "Default")
      (node (ref "D217") (pin "1") (pinfunction "A_1") (pintype "passive"))
      (node (ref "S217") (pin "1") (pinfunction "1_1") (pintype "passive"))
    )
    (net (code "35") (name "Net-(D218-A)") (class "Default")
      (node (ref "D218") (pin "1") (pinfunction "A_1") (pintype "passive"))
      (node (ref "S218") (pin "1") (pinfunction "1_1") (pintype "passive"))
    )
    (net (code "36") (name "Net-(D219-A)") (class "Default")
      (node (ref "D219") (pin "1") (pinfunction "A_1") (pintype "passive"))
      (node (ref "S219") (pin "1") (pinfunction "1_1") (pintype "passive"))
    )
    (net (code "37") (name "Net-(D220-A)") (class "Default")
      (node (ref "D220") (pin "1") (pinfunction "A_1") (pintype "passive"))
      (node (ref "S220") (pin "1") (pinfunction "1_1") (pintype "passive"))
    )
    (net (code "38") (name "Net-(D221-A)") (class "Default")
      (node (ref "D221") (pin "1") (pinfunction "A_1") (pintype "passive"))
      (node (ref "S221") (pin "1") (pinfunction "1_1") (pintype "passive"))
    )
    (net (code "39") (name "Net-(D222-A)") (class "Default")
      (node (ref "D222") (pin "1") (pinfunction "A_1") (pintype "passive"))
      (node (ref "S222") (pin "1") (pinfunction "1_1") (pintype "passive"))
    )
    (net (code "40") (name "Net-(D223-A)") (class "Default")
      (node (ref "D223") (pin "1") (pinfunction "A_1") (pintype "passive"))
      (node (ref "S223") (pin "1") (pinfunction "1_1") (pintype "passive"))
    )
    (net (code "41") (name "Net-(D224-A)") (class "Default")
      (node (ref "D224") (pin "1") (pinfunction "A_1") (pintype "passive"))
      (node (ref "S224") (pin "1") (pinfunction "1_1") (pintype "passive"))
    )
    (net (code "42") (name "Net-(D225-A)") (class "Default")
      (node (ref "D225") (pin "1") (pinfunction "A_1") (pintype "passive"))
      (node (ref "S225") (pin "1") (pinfunction "1_1") (pintype "passive"))
    )
    (net (code "43") (name "Net-(D226-A)") (class "Default")
      (node (ref "D226") (pin "1") (pinfunction "A_1") (pintype "passive"))
      (node (ref "S226") (pin "1") (pinfunction "1_1") (pintype "passive"))
    )
    (net (code "44") (name "Net-(D227-A)") (class "Default")
      (node (ref "D227") (pin "1") (pinfunction "A_1") (pintype "passive"))
      (node (ref "S227") (pin "1") (pinfunction "1_1") (pintype "passive"))
    )
    (net (code "45") (name "Net-(D228-A)") (class "Default")
      (node (ref "D228") (pin "1") (pinfunction "A_1") (pintype "passive"))
      (node (ref "S228") (pin "1") (pinfunction "1_1") (pintype "passive"))
    )
    (net (code "46") (name "Net-(D229-A)") (class "Default")
      (node (ref "D229") (pin "1") (pinfunction "A_1") (pintype "passive"))
      (node (ref "S229") (pin "1") (pinfunction "1_1") (pintype "passive"))
    )
    (net (code "47") (name "Net-(D230-A)") (class "Default")
      (node (ref "D230") (pin "1") (pinfunction "A_1") (pintype "passive"))
      (node (ref "S230") (pin "1") (pinfunction "1_1") (pintype "passive"))
    )
    (net (code "48") (name "Net-(D231-A)") (class "Default")
      (node (ref "D231") (pin "1") (pinfunction "A_1") (pintype "passive"))
      (node (ref "S231") (pin "1") (pinfunction "1_1") (pintype "passive"))
    )
    (net (code "49") (name "Net-(D232-A)") (class "Default")
      (node (ref "D232") (pin "1") (pinfunction "A_1") (pintype "passive"))
      (node (ref "S232") (pin "1") (pinfunction "1_1") (pintype "passive"))
    )
    (net (code "50") (name "Net-(D233-A)") (class "Default")
      (node (ref "D233") (pin "1") (pinfunction "A_1") (pintype "passive"))
      (node (ref "S233") (pin "1") (pinfunction "1_1") (pintype "passive"))
    )
    (net (code "51") (name "Net-(D234-A)") (class "Default")
      (node (ref "D234") (pin "1") (pinfunction "A_1") (pintype "passive"))
      (node (ref "S234") (pin "1") (pinfunction "1_1") (pintype "passive"))
    )
    (net (code "52") (name "Net-(D235-A)") (class "Default")
      (node (ref "D235") (pin "1") (pinfunction "A_1") (pintype "passive"))
      (node (ref "S235") (pin "1") (pinfunction "1_1") (pintype "passive"))
    )
    (net (code "53") (name "Net-(D236-A)") (class "Default")
      (node (ref "D236") (pin "1") (pinfunction "A_1") (pintype "passive"))
      (node (ref "S236") (pin "1") (pinfunction "1_1") (pintype "passive"))
    )
    (net (code "54") (name "Net-(D237-A)") (class "Default")
      (node (ref "D237") (pin "1") (pinfunction "A_1") (pintype "passive"))
      (node (ref "S237") (pin "1") (pinfunction "1_1") (pintype "passive"))
    )
    (net (code "55") (name "Net-(D238-A)") (class "Default")
      (node (ref "D238") (pin "1") (pinfunction "A_1") (pintype "passive"))
      (node (ref "S238") (pin "1") (pinfunction "1_1") (pintype "passive"))
    )
    (net (code "56") (name "Net-(D239-A)") (class "Default")
      (node (ref "D239") (pin "1") (pinfunction "A_1") (pintype "passive"))
      (node (ref "S239") (pin "1") (pinfunction "1_1") (pintype "passive"))
    )
    (net (code "57") (name "Net-(D240-A)") (class "Default")
      (node (ref "D240") (pin "1") (pinfunction "A_1") (pintype "passive"))
      (node (ref "S240") (pin "1") (pinfunction "1_1") (pintype "passive"))
    )
    (net (code "58") (name "Net-(D241-A)") (class "Default")
      (node (ref "D241") (pin "1") (pinfunction "A_1") (pintype "passive"))
      (node (ref "S241") (pin "1") (pinfunction "1_1") (pintype "passive"))
    )
    (net (code "59") (name "Net-(D242-A)") (class "Default")
      (node (ref "D242") (pin "1") (pinfunction "A_1") (pintype "passive"))
      (node (ref "S242") (pin "1") (pinfunction "1_1") (pintype "passive"))
    )
    (net (code "60") (name "Net-(D243-A)") (class "Default")
      (node (ref "D243") (pin "1") (pinfunction "A_1") (pintype "passive"))
      (node (ref "S243") (pin "1") (pinfunction "1_1") (pintype "passive"))
    )
    (net (code "61") (name "Net-(D244-A)") (class "Default")
      (node (ref "D244") (pin "1") (pinfunction "A_1") (pintype "passive"))
      (node (ref "S244") (pin "1") (pinfunction "1_1") (pintype "passive"))
    )
    (net (code "62") (name "Net-(D245-A)") (class "Default")
      (node (ref "D245") (pin "1") (pinfunction "A_1") (pintype "passive"))
      (node (ref "S245") (pin "1") (pinfunction "1_1") (pintype "passive"))
    )
    (net (code "63") (name "Net-(D246-A)") (class "Default")
      (node (ref "D246") (pin "1") (pinfunction "A_1") (pintype "passive"))
      (node (ref "S246") (pin "1") (pinfunction "1_1") (pintype "passive"))
    )
    (net (code "64") (name "Net-(D247-A)") (class "Default")
      (node (ref "D247") (pin "1") (pinfunction "A_1") (pintype "passive"))
      (node (ref "S247") (pin "1") (pinfunction "1_1") (pintype "passive"))
    )
    (net (code "65") (name "Net-(D248-A)") (class "Default")
      (node (ref "D248") (pin "1") (pinfunction "A_1") (pintype "passive"))
      (node (ref "S248") (pin "1") (pinfunction "1_1") (pintype "passive"))
    )
    (net (code "66") (name "Net-(D249-A)") (class "Default")
      (node (ref "D249") (pin "1") (pinfunction "A_1") (pintype "passive"))
      (node (ref "S249") (pin "1") (pinfunction "1_1") (pintype "passive"))
    )
    (net (code "67") (name "Net-(D250-A)") (class "Default")
      (node (ref "D250") (pin "1") (pinfunction "A_1") (pintype "passive"))
      (node (ref "S250") (pin "1") (pinfunction "1_1") (pintype "passive"))
    )
    (net (code "68") (name "Net-(D251-A)") (class "Default")
      (node (ref "D251") (pin "1") (pinfunction "A_1") (pintype "passive"))
      (node (ref "S251") (pin "1") (pinfunction "1_1") (pintype "passive"))
    )
    (net (code "69") (name "Net-(D252-A)") (class "Default")
      (node (ref "D252") (pin "1") (pinfunction "A_1") (pintype "passive"))
      (node (ref "S252") (pin "1") (pinfunction "1_1") (pintype "passive"))
    )
    (net (code "70") (name "Net-(D253-A)") (class "Default")
      (node (ref "D253") (pin "1") (pinfunction "A_1") (pintype "passive"))
      (node (ref "S253") (pin "1") (pinfunction "1_1") (pintype "passive"))
    )
    (net (code "71") (name "Net-(D254-A)") (class "Default")
      (node (ref "D254") (pin "1") (pinfunction "A_1") (pintype "passive"))
      (node (ref "S254") (pin "1") (pinfunction "1_1") (pintype "passive"))
    )
    (net (code "72") (name "Net-(D256-A)") (class "Default")
      (node (ref "D256") (pin "1") (pinfunction "A_1") (pintype "passive"))
      (node (ref "S256") (pin "1") (pinfunction "1_1") (pintype "passive"))
    )
    (net (code "73") (name "Net-(D257-A)") (class "Default")
      (node (ref "D257") (pin "1") (pinfunction "A_1") (pintype "passive"))
      (node (ref "S257") (pin "1") (pinfunction "1_1") (pintype "passive"))
    )
    (net (code "74") (name "Net-(D258-A)") (class "Default")
      (node (ref "D258") (pin "1") (pinfunction "A_1") (pintype "passive"))
      (node (ref "S258") (pin "1") (pinfunction "1_1") (pintype "passive"))
    )
    (net (code "75") (name "Net-(D259-A)") (class "Default")
      (node (ref "D259") (pin "1") (pinfunction "A_1") (pintype "passive"))
      (node (ref "S259") (pin "1") (pinfunction "1_1") (pintype "passive"))
    )
    (net (code "76") (name "Net-(D260-A)") (class "Default")
      (node (ref "D260") (pin "1") (pinfunction "A_1") (pintype "passive"))
      (node (ref "S260") (pin "1") (pinfunction "1_1") (pintype "passive"))
    )
    (net (code "77") (name "Net-(D261-A)") (class "Default")
      (node (ref "D261") (pin "1") (pinfunction "A_1") (pintype "passive"))
      (node (ref "S261") (pin "1") (pinfunction "1_1") (pintype "passive"))
    )
    (net (code "78") (name "Net-(D262-A)") (class "Default")
      (node (ref "D262") (pin "1") (pinfunction "A_1") (pintype "passive"))
      (node (ref "S262") (pin "1") (pinfunction "1_1") (pintype "passive"))
    )
    (net (code "79") (name "Net-(D263-A)") (class "Default")
      (node (ref "D263") (pin "1") (pinfunction "A_1") (pintype "passive"))
      (node (ref "S263") (pin "1") (pinfunction "1_1") (pintype "passive"))
    )
    (net (code "80") (name "Net-(D264-A)") (class "Default")
      (node (ref "D264") (pin "1") (pinfunction "A_1") (pintype "passive"))
      (node (ref "S264") (pin "1") (pinfunction "1_1") (pintype "passive"))
    )
    (net (code "81") (name "Net-(D265-A)") (class "Default")
      (node (ref "D265") (pin "1") (pinfunction "A_1") (pintype "passive"))
      (node (ref "S265") (pin "1") (pinfunction "1_1") (pintype "passive"))
    )
    (net (code "82") (name "Net-(D266-A)") (class "Default")
      (node (ref "D266") (pin "1") (pinfunction "A_1") (pintype "passive"))
      (node (ref "S266") (pin "1") (pinfunction "1_1") (pintype "passive"))
    )
    (net (code "83") (name "Net-(D269-A)") (class "Default")
      (node (ref "D269") (pin "1") (pinfunction "A_1") (pintype "passive"))
      (node (ref "S269") (pin "1") (pinfunction "1_1") (pintype "passive"))
    )
  )
)
